# PenguinPi.net
KiCad netlist of a schematic drawn in Altium Designer
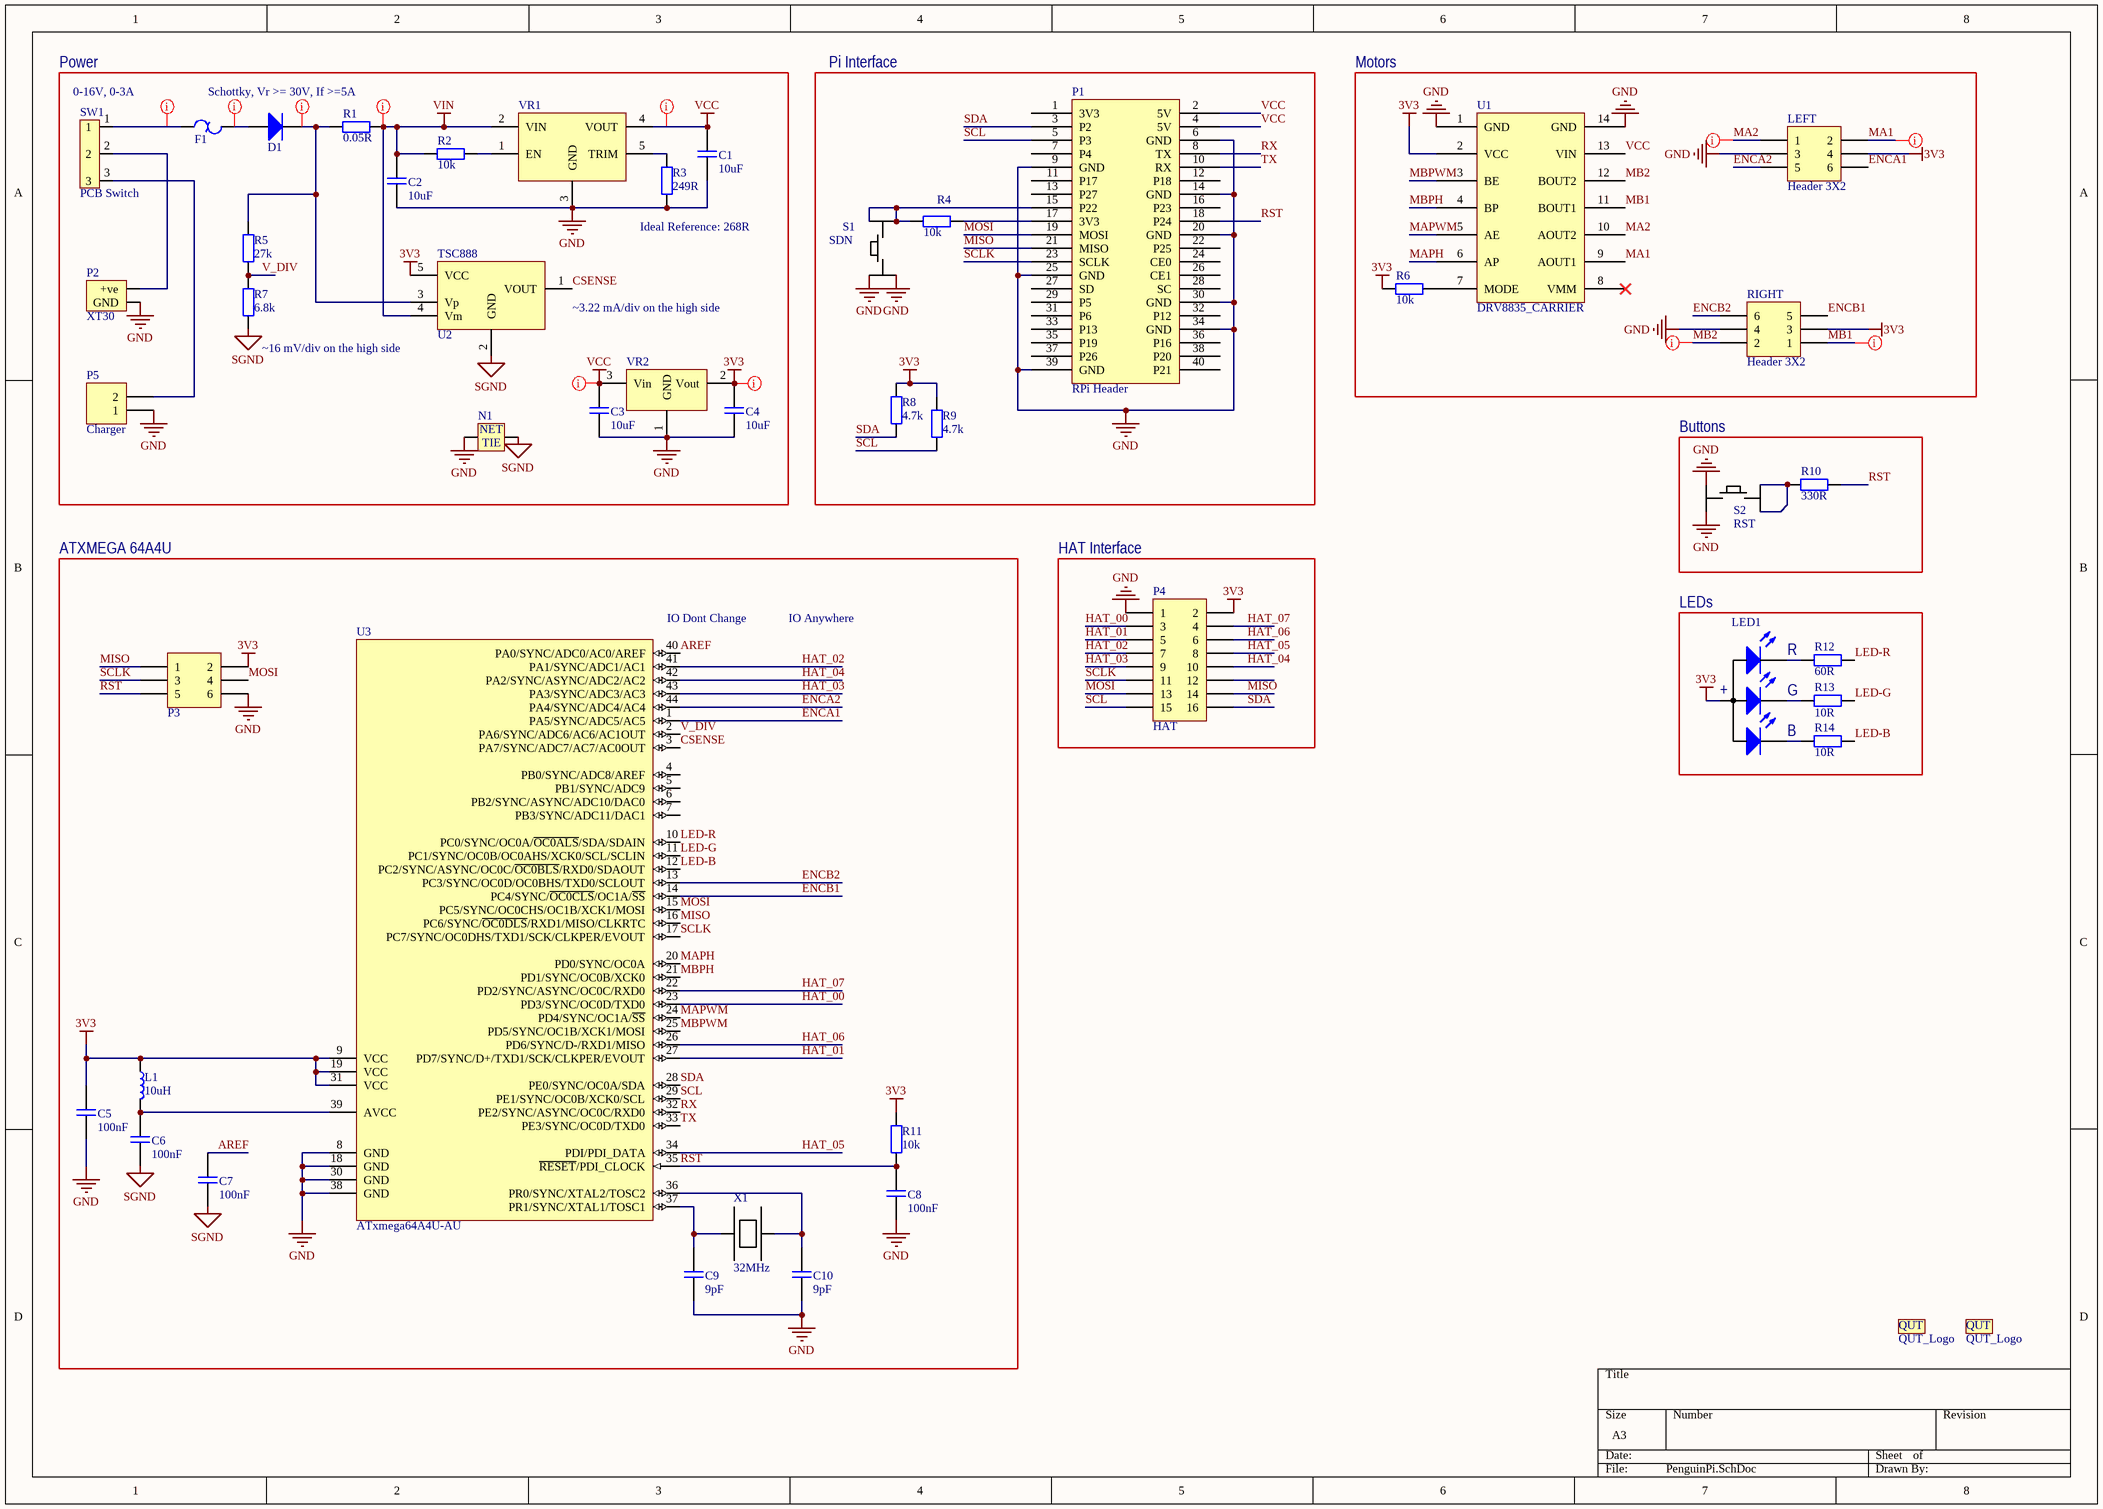
[diagram p0: PenguinPi.SchDoc]

(export (version "E")
  (design (tool "Eeschema 10.0.6"))
  (components
    (comp (ref "C1")
      (value "10uF")
      (footprint "CAPC2012X07N")
      (description "Surface mount capacitor")
      (fields (field (name "Comment") "CAP SMD"))
      (libsource (lib "Penguin") (part "CAP SMD"))
    )
    (comp (ref "C2")
      (value "10uF")
      (footprint "CAPC2012X07N")
      (description "Surface mount capacitor")
      (fields (field (name "Comment") "CAP SMD"))
      (libsource (lib "Penguin") (part "CAP SMD"))
    )
    (comp (ref "C3")
      (value "10uF")
      (footprint "CAPC2012X07N")
      (description "Surface mount capacitor")
      (fields (field (name "Comment") "CAP SMD"))
      (libsource (lib "Penguin") (part "CAP SMD"))
    )
    (comp (ref "C4")
      (value "10uF")
      (footprint "CAPC2012X07N")
      (description "Surface mount capacitor")
      (fields (field (name "Comment") "CAP SMD"))
      (libsource (lib "Penguin") (part "CAP SMD"))
    )
    (comp (ref "C5")
      (value "100nF")
      (footprint "CAPC2012X07N")
      (description "Surface mount capacitor")
      (fields (field (name "Comment") "CAP SMD"))
      (libsource (lib "Penguin") (part "CAP SMD"))
    )
    (comp (ref "C6")
      (value "100nF")
      (footprint "CAPC2012X07N")
      (description "Surface mount capacitor")
      (fields (field (name "Comment") "CAP SMD"))
      (libsource (lib "Penguin") (part "CAP SMD"))
    )
    (comp (ref "C7")
      (value "100nF")
      (footprint "CAPC2012X07N")
      (description "Surface mount capacitor")
      (fields (field (name "Comment") "CAP SMD"))
      (libsource (lib "Penguin") (part "CAP SMD"))
    )
    (comp (ref "C8")
      (value "100nF")
      (footprint "CAPC2012X07N")
      (description "Surface mount capacitor")
      (fields (field (name "Comment") "CAP SMD"))
      (libsource (lib "Penguin") (part "CAP SMD"))
    )
    (comp (ref "C9")
      (value "9pF")
      (footprint "CAPC2012X07N")
      (description "Surface mount capacitor")
      (fields (field (name "Comment") "CAP SMD"))
      (libsource (lib "Penguin") (part "CAP SMD"))
    )
    (comp (ref "C10")
      (value "9pF")
      (footprint "CAPC2012X07N")
      (description "Surface mount capacitor")
      (fields (field (name "Comment") "CAP SMD"))
      (libsource (lib "Penguin") (part "CAP SMD"))
    )
    (comp (ref "D1")
      (value "SMD DIODE")
      (footprint "SODFL470X110-2N")
      (description "Surface mount Diode")
      (libsource (lib "Penguin") (part "SMD DIODE"))
    )
    (comp (ref "F1")
      (value "RGEF250")
      (footprint "MF-MSMF250/16X-2")
      (description "PPTC Thermal Fuse")
      (libsource (lib "Penguin") (part "RGEF250"))
    )
    (comp (ref "L1")
      (value "10uH")
      (footprint "CM322522")
      (description "Surface Mount Inductor - varying sizes")
      (fields (field (name "Comment") "INDUCTOR SMD"))
      (libsource (lib "Penguin") (part "INDUCTOR SMD"))
    )
    (comp (ref "LED1")
      (value "RGB SMD")
      (footprint "RGB SMD")
      (description "ASMB-MTB1-0A3A2")
      (libsource (lib "Penguin") (part "RGB SMD"))
    )
    (comp (ref "LEFT")
      (value "Header 3X2")
      (footprint "HDR2X3")
      (description "Header, 3-Pin, Dual row")
      (fields (field (name "PUBLISHER") "Altium Limited"))
      (libsource (lib "Miscellaneous Connectors") (part "Header 3X2"))
    )
    (comp (ref "LG1") (value "QUT_Logo") (footprint "QUT_Logo") (libsource (lib "Penguin") (part "QUT_Logo")))
    (comp (ref "LG2") (value "QUT_Logo") (footprint "QUT_Logo") (libsource (lib "Penguin") (part "QUT_Logo")))
    (comp (ref "N1")
      (value "NETTIE")
      (footprint "NETTIE-SMD-5mil")
      (libsource (lib "Penguin") (part "NETTIE"))
    )
    (comp (ref "P1")
      (value "RPi Header")
      (footprint "RPI 2 Header")
      (description "GPIO connector for Raspberry Pi Microcomputer")
      (libsource (lib "Penguin") (part "RPi 2 Header"))
    )
    (comp (ref "P2") (value "XT30") (footprint "XT30 - PCB mount") (libsource (lib "QUT") (part "XT30")))
    (comp (ref "P3")
      (value "Header 3x2")
      (footprint "Header 3x2 nonstandard")
      (description "3 by 2 header, staggered pin arrangement")
      (libsource (lib "Penguin") (part "Header 3x2 Staggered"))
    )
    (comp (ref "P4")
      (value "HAT")
      (footprint "HDR2X8")
      (description "Header, 8-Pin, Dual row")
      (fields (field (name "PUBLISHER") "Altium Limited"))
      (libsource (lib "Miscellaneous Connectors") (part "Header 8X2"))
    )
    (comp (ref "P5")
      (value "Charger")
      (footprint "HDR1X2")
      (description "Header, 2-Pin")
      (fields (field (name "PUBLISHER") "Altium Limited"))
      (libsource (lib "Miscellaneous Connectors") (part "Header 2"))
    )
    (comp (ref "R1")
      (value "0.05R")
      (footprint "RESC3216X06M")
      (description "0805 surface mount resistor")
      (fields (field (name "Comment") "RES SMD"))
      (libsource (lib "") (part "RES SMD_3"))
    )
    (comp (ref "R2")
      (value "10k")
      (footprint "RESC2012X07N")
      (description "0805 surface mount resistor")
      (fields (field (name "Comment") "RES SMD"))
      (libsource (lib "Penguin") (part "RES SMD"))
    )
    (comp (ref "R3")
      (value "249R")
      (footprint "RESC2012X07N")
      (description "0805 surface mount resistor")
      (fields (field (name "Comment") "RES SMD"))
      (libsource (lib "") (part "RES SMD_1"))
    )
    (comp (ref "R4")
      (value "10k")
      (footprint "RESC2012X07N")
      (description "0805 surface mount resistor")
      (fields (field (name "Comment") "RES SMD"))
      (libsource (lib "") (part "RES SMD_2"))
    )
    (comp (ref "R5")
      (value "27k")
      (footprint "RESC2012X07N")
      (description "0805 surface mount resistor")
      (fields (field (name "Comment") "RES SMD"))
      (libsource (lib "") (part "RES SMD_1"))
    )
    (comp (ref "R6")
      (value "10k")
      (footprint "RESC2012X07N")
      (description "0805 surface mount resistor")
      (fields (field (name "Comment") "RES SMD"))
      (libsource (lib "") (part "RES SMD_2"))
    )
    (comp (ref "R7")
      (value "6.8k")
      (footprint "RESC2012X07N")
      (description "0805 surface mount resistor")
      (fields (field (name "Comment") "RES SMD"))
      (libsource (lib "") (part "RES SMD_1"))
    )
    (comp (ref "R8")
      (value "4.7k")
      (footprint "RESC2012X07N")
      (description "0805 surface mount resistor")
      (fields (field (name "Comment") "RES SMD"))
      (libsource (lib "") (part "RES SMD_1"))
    )
    (comp (ref "R9")
      (value "4.7k")
      (footprint "RESC2012X07N")
      (description "0805 surface mount resistor")
      (fields (field (name "Comment") "RES SMD"))
      (libsource (lib "") (part "RES SMD_1"))
    )
    (comp (ref "R10")
      (value "330R")
      (footprint "RESC2012X07N")
      (description "0805 surface mount resistor")
      (fields (field (name "Comment") "RES SMD"))
      (libsource (lib "") (part "RES SMD_2"))
    )
    (comp (ref "R11")
      (value "10k")
      (footprint "RESC2012X07N")
      (description "0805 surface mount resistor")
      (fields (field (name "Comment") "RES SMD"))
      (libsource (lib "") (part "RES SMD_1"))
    )
    (comp (ref "R12")
      (value "60R")
      (footprint "RESC2012X07N")
      (description "0805 surface mount resistor")
      (fields (field (name "Comment") "RES SMD"))
      (libsource (lib "") (part "RES SMD_2"))
    )
    (comp (ref "R13")
      (value "10R")
      (footprint "RESC2012X07N")
      (description "0805 surface mount resistor")
      (fields (field (name "Comment") "RES SMD"))
      (libsource (lib "") (part "RES SMD_2"))
    )
    (comp (ref "R14")
      (value "10R")
      (footprint "RESC2012X07N")
      (description "0805 surface mount resistor")
      (fields (field (name "Comment") "RES SMD"))
      (libsource (lib "") (part "RES SMD_2"))
    )
    (comp (ref "RIGHT")
      (value "Header 3X2")
      (footprint "HDR2X3")
      (description "Header, 3-Pin, Dual row")
      (fields (field (name "PUBLISHER") "Altium Limited"))
      (libsource (lib "") (part "Header 3X2_1"))
    )
    (comp (ref "S1")
      (value "SDN")
      (footprint "E-SWITCH-TL3342")
      (description "TL 3342 surface mount pushbutton")
      (libsource (lib "Penguin") (part "E-SWITCH-PUSHBUTTON"))
    )
    (comp (ref "S2")
      (value "RST")
      (footprint "E-SWITCH-TL3342")
      (description "TL 3342 surface mount pushbutton")
      (libsource (lib "Penguin") (part "E-SWITCH-PUSHBUTTON"))
    )
    (comp (ref "SW1")
      (value "PCB Switch")
      (footprint "PCB Switch")
      (libsource (lib "PenguinPi_v2") (part "PCB Switch"))
    )
    (comp (ref "U1")
      (value "DRV8835_CARRIER")
      (footprint "DRV8835_CARRIER")
      (description "DRV8835 Motor Controller")
      (libsource (lib "Penguin") (part "DRV8835_CARRIER"))
    )
    (comp (ref "U2")
      (value "TSC888")
      (footprint "SOT95P280X145-5N")
      (description "Curent Sense Amplifier")
      (libsource (lib "Penguin") (part "TSC888"))
    )
    (comp (ref "U3")
      (value "ATxmega64A4U-AU")
      (footprint "44A_L")
      (fields (field (name "MANUFACTURER") "Atmel"))
      (libsource (lib "Altium Content Vault") (part "CMP-0094-00068-2"))
    )
    (comp (ref "VR1")
      (value "MURATA_OKR-T3-W12C")
      (footprint "MURATA_OKR-Tn")
      (description "5V 3A switching voltage regulator")
      (libsource (lib "Penguin") (part "MURATA_OKR-T3-W12C"))
    )
    (comp (ref "VR2")
      (value "3V3 LDO")
      (footprint "SOT230P700X180-4N")
      (description "3.3 V Low Dropout Regulator")
      (libsource (lib "Penguin") (part "3V3 LDO"))
    )
    (comp (ref "X1")
      (value "32MHz")
      (footprint "XTAL AV Series")
      (fields (field (name "MAN PART NO") "X1E0000210162"))
      (libsource (lib "QUT") (part "XTAL"))
    )
  )
  (nets
    (net (code "1") (name "/AREF") (class "Default")
      (node (ref "C7") (pin "2") (pinfunction "K_2") (pintype "passive"))
      (node (ref "U3") (pin "40") (pinfunction "PA0/SYNC/ADC0/AC0/AREF_40") (pintype "bidirectional"))
    )
    (net (code "2") (name "/CSENSE") (class "Default")
      (node (ref "U2") (pin "1") (pinfunction "VOUT_1") (pintype "passive"))
      (node (ref "U3") (pin "3") (pinfunction "PA7/SYNC/ADC7/AC7/AC0OUT_3") (pintype "bidirectional"))
    )
    (net (code "3") (name "/ENCA1") (class "Default")
      (node (ref "LEFT") (pin "6") (pinfunction "6_6") (pintype "passive"))
      (node (ref "U3") (pin "1") (pinfunction "PA5/SYNC/ADC5/AC5_1") (pintype "bidirectional"))
    )
    (net (code "4") (name "/ENCA2") (class "Default")
      (node (ref "LEFT") (pin "5") (pinfunction "5_5") (pintype "passive"))
      (node (ref "U3") (pin "44") (pinfunction "PA4/SYNC/ADC4/AC4_44") (pintype "bidirectional"))
    )
    (net (code "5") (name "/ENCB1") (class "Default")
      (node (ref "RIGHT") (pin "5") (pinfunction "5_5") (pintype "passive"))
      (node (ref "U3") (pin "14") (pinfunction "PC4/SYNC/~{OC0CLS}/OC1A/~{SS}_14") (pintype "bidirectional"))
    )
    (net (code "6") (name "/ENCB2") (class "Default")
      (node (ref "RIGHT") (pin "6") (pinfunction "6_6") (pintype "passive"))
      (node (ref "U3") (pin "13") (pinfunction "PC3/SYNC/OC0D/OC0BHS/TXD0/SCLOUT_13") (pintype "bidirectional"))
    )
    (net (code "7") (name "/HAT_00") (class "Default")
      (node (ref "P4") (pin "3") (pinfunction "3_3") (pintype "passive"))
      (node (ref "U3") (pin "23") (pinfunction "PD3/SYNC/OC0D/TXD0_23") (pintype "bidirectional"))
    )
    (net (code "8") (name "/HAT_01") (class "Default")
      (node (ref "P4") (pin "5") (pinfunction "5_5") (pintype "passive"))
      (node (ref "U3") (pin "27") (pinfunction "PD7/SYNC/D+/TXD1/SCK/CLKPER/EVOUT_27") (pintype "bidirectional"))
    )
    (net (code "9") (name "/HAT_02") (class "Default")
      (node (ref "P4") (pin "7") (pinfunction "7_7") (pintype "passive"))
      (node (ref "U3") (pin "41") (pinfunction "PA1/SYNC/ADC1/AC1_41") (pintype "bidirectional"))
    )
    (net (code "10") (name "/HAT_03") (class "Default")
      (node (ref "P4") (pin "9") (pinfunction "9_9") (pintype "passive"))
      (node (ref "U3") (pin "43") (pinfunction "PA3/SYNC/ADC3/AC3_43") (pintype "bidirectional"))
    )
    (net (code "11") (name "/HAT_04") (class "Default")
      (node (ref "P4") (pin "10") (pinfunction "10_10") (pintype "passive"))
      (node (ref "U3") (pin "42") (pinfunction "PA2/SYNC/ASYNC/ADC2/AC2_42") (pintype "bidirectional"))
    )
    (net (code "12") (name "/HAT_05") (class "Default")
      (node (ref "P4") (pin "8") (pinfunction "8_8") (pintype "passive"))
      (node (ref "U3") (pin "34") (pinfunction "PDI/PDI_DATA_34") (pintype "bidirectional"))
    )
    (net (code "13") (name "/HAT_06") (class "Default")
      (node (ref "P4") (pin "6") (pinfunction "6_6") (pintype "passive"))
      (node (ref "U3") (pin "26") (pinfunction "PD6/SYNC/D-/RXD1/MISO_26") (pintype "bidirectional"))
    )
    (net (code "14") (name "/HAT_07") (class "Default")
      (node (ref "P4") (pin "4") (pinfunction "4_4") (pintype "passive"))
      (node (ref "U3") (pin "22") (pinfunction "PD2/SYNC/ASYNC/OC0C/RXD0_22") (pintype "bidirectional"))
    )
    (net (code "15") (name "/LED-B") (class "Default")
      (node (ref "R14") (pin "2") (pinfunction "2_2") (pintype "passive"))
      (node (ref "U3") (pin "12") (pinfunction "PC2/SYNC/ASYNC/OC0C/~{OC0BLS}/RXD0/SDAOUT_12") (pintype "bidirectional"))
    )
    (net (code "16") (name "/LED-G") (class "Default")
      (node (ref "R13") (pin "2") (pinfunction "2_2") (pintype "passive"))
      (node (ref "U3") (pin "11") (pinfunction "PC1/SYNC/OC0B/OC0AHS/XCK0/SCL/SCLIN_11") (pintype "bidirectional"))
    )
    (net (code "17") (name "/LED-R") (class "Default")
      (node (ref "R12") (pin "2") (pinfunction "2_2") (pintype "passive"))
      (node (ref "U3") (pin "10") (pinfunction "PC0/SYNC/OC0A/~{OC0ALS}/SDA/SDAIN_10") (pintype "bidirectional"))
    )
    (net (code "18") (name "/MA1") (class "Default")
      (node (ref "LEFT") (pin "2") (pinfunction "2_2") (pintype "passive"))
      (node (ref "U1") (pin "9") (pinfunction "AOUT1_9") (pintype "passive"))
    )
    (net (code "19") (name "/MA2") (class "Default")
      (node (ref "LEFT") (pin "1") (pinfunction "1_1") (pintype "passive"))
      (node (ref "U1") (pin "10") (pinfunction "AOUT2_10") (pintype "passive"))
    )
    (net (code "20") (name "/MAPH") (class "Default")
      (node (ref "U1") (pin "6") (pinfunction "AP_6") (pintype "passive"))
      (node (ref "U3") (pin "20") (pinfunction "PD0/SYNC/OC0A_20") (pintype "bidirectional"))
    )
    (net (code "21") (name "/MAPWM") (class "Default")
      (node (ref "U1") (pin "5") (pinfunction "AE_5") (pintype "passive"))
      (node (ref "U3") (pin "24") (pinfunction "PD4/SYNC/OC1A/~{SS}_24") (pintype "bidirectional"))
    )
    (net (code "22") (name "/MB1") (class "Default")
      (node (ref "RIGHT") (pin "1") (pinfunction "1_1") (pintype "passive"))
      (node (ref "U1") (pin "11") (pinfunction "BOUT1_11") (pintype "passive"))
    )
    (net (code "23") (name "/MB2") (class "Default")
      (node (ref "RIGHT") (pin "2") (pinfunction "2_2") (pintype "passive"))
      (node (ref "U1") (pin "12") (pinfunction "BOUT2_12") (pintype "passive"))
    )
    (net (code "24") (name "/MBPH") (class "Default")
      (node (ref "U1") (pin "4") (pinfunction "BP_4") (pintype "passive"))
      (node (ref "U3") (pin "21") (pinfunction "PD1/SYNC/OC0B/XCK0_21") (pintype "bidirectional"))
    )
    (net (code "25") (name "/MBPWM") (class "Default")
      (node (ref "U1") (pin "3") (pinfunction "BE_3") (pintype "passive"))
      (node (ref "U3") (pin "25") (pinfunction "PD5/SYNC/OC1B/XCK1/MOSI_25") (pintype "bidirectional"))
    )
    (net (code "26") (name "/MISO") (class "Default")
      (node (ref "P1") (pin "21") (pinfunction "MISO_21") (pintype "passive"))
      (node (ref "P3") (pin "1") (pinfunction "1_1") (pintype "passive"))
      (node (ref "P4") (pin "14") (pinfunction "14_14") (pintype "passive"))
      (node (ref "U3") (pin "16") (pinfunction "PC6/SYNC/~{OC0DLS}/RXD1/MISO/CLKRTC_16") (pintype "bidirectional"))
    )
    (net (code "27") (name "/MOSI") (class "Default")
      (node (ref "P1") (pin "19") (pinfunction "MOSI_19") (pintype "passive"))
      (node (ref "P3") (pin "4") (pinfunction "4_4") (pintype "passive"))
      (node (ref "P4") (pin "13") (pinfunction "13_13") (pintype "passive"))
      (node (ref "U3") (pin "15") (pinfunction "PC5/SYNC/OC0CHS/OC1B/XCK1/MOSI_15") (pintype "bidirectional"))
    )
    (net (code "28") (name "/RST") (class "Default")
      (node (ref "C8") (pin "2") (pinfunction "K_2") (pintype "passive"))
      (node (ref "P1") (pin "18") (pinfunction "P24_18") (pintype "passive"))
      (node (ref "P3") (pin "5") (pinfunction "5_5") (pintype "passive"))
      (node (ref "R10") (pin "2") (pinfunction "2_2") (pintype "passive"))
      (node (ref "R11") (pin "1") (pinfunction "1_1") (pintype "passive"))
      (node (ref "U3") (pin "35") (pinfunction "~{RESET}/PDI_CLOCK_35") (pintype "input"))
    )
    (net (code "29") (name "/RX") (class "Default")
      (node (ref "P1") (pin "8") (pinfunction "TX_8") (pintype "passive"))
      (node (ref "U3") (pin "32") (pinfunction "PE2/SYNC/ASYNC/OC0C/RXD0_32") (pintype "bidirectional"))
    )
    (net (code "30") (name "/SCL") (class "Default")
      (node (ref "P1") (pin "5") (pinfunction "P3_5") (pintype "passive"))
      (node (ref "P4") (pin "15") (pinfunction "15_15") (pintype "passive"))
      (node (ref "R9") (pin "1") (pinfunction "1_1") (pintype "passive"))
      (node (ref "U3") (pin "29") (pinfunction "PE1/SYNC/OC0B/XCK0/SCL_29") (pintype "bidirectional"))
    )
    (net (code "31") (name "/SCLK") (class "Default")
      (node (ref "P1") (pin "23") (pinfunction "SCLK_23") (pintype "passive"))
      (node (ref "P3") (pin "3") (pinfunction "3_3") (pintype "passive"))
      (node (ref "P4") (pin "11") (pinfunction "11_11") (pintype "passive"))
      (node (ref "U3") (pin "17") (pinfunction "PC7/SYNC/OC0DHS/TXD1/SCK/CLKPER/EVOUT_17") (pintype "bidirectional"))
    )
    (net (code "32") (name "/SDA") (class "Default")
      (node (ref "P1") (pin "3") (pinfunction "P2_3") (pintype "passive"))
      (node (ref "P4") (pin "16") (pinfunction "16_16") (pintype "passive"))
      (node (ref "R8") (pin "1") (pinfunction "1_1") (pintype "passive"))
      (node (ref "U3") (pin "28") (pinfunction "PE0/SYNC/OC0A/SDA_28") (pintype "bidirectional"))
    )
    (net (code "33") (name "/TX") (class "Default")
      (node (ref "P1") (pin "10") (pinfunction "RX_10") (pintype "passive"))
      (node (ref "U3") (pin "33") (pinfunction "PE3/SYNC/OC0D/TXD0_33") (pintype "bidirectional"))
    )
    (net (code "34") (name "/V_DIV") (class "Default")
      (node (ref "R5") (pin "1") (pinfunction "1_1") (pintype "passive"))
      (node (ref "R7") (pin "2") (pinfunction "2_2") (pintype "passive"))
      (node (ref "U3") (pin "2") (pinfunction "PA6/SYNC/ADC6/AC6/AC1OUT_2") (pintype "bidirectional"))
    )
    (net (code "35") (name "3V3") (class "Default")
      (node (ref "C4") (pin "2") (pinfunction "K_2") (pintype "passive"))
      (node (ref "C5") (pin "2") (pinfunction "K_2") (pintype "passive"))
      (node (ref "L1") (pin "1") (pinfunction "Anode_1") (pintype "passive"))
      (node (ref "LED1") (pin "4") (pinfunction "A_4") (pintype "passive"))
      (node (ref "LEFT") (pin "4") (pinfunction "4_4") (pintype "passive"))
      (node (ref "P3") (pin "2") (pinfunction "2_2") (pintype "passive"))
      (node (ref "P4") (pin "2") (pinfunction "2_2") (pintype "passive"))
      (node (ref "R11") (pin "2") (pinfunction "2_2") (pintype "passive"))
      (node (ref "R6") (pin "1") (pinfunction "1_1") (pintype "passive"))
      (node (ref "R8") (pin "2") (pinfunction "2_2") (pintype "passive"))
      (node (ref "R9") (pin "2") (pinfunction "2_2") (pintype "passive"))
      (node (ref "RIGHT") (pin "3") (pinfunction "3_3") (pintype "passive"))
      (node (ref "U1") (pin "2") (pinfunction "VCC_2") (pintype "passive"))
      (node (ref "U2") (pin "5") (pinfunction "VCC_5") (pintype "passive"))
      (node (ref "U3") (pin "19") (pinfunction "VCC_19") (pintype "power_in"))
      (node (ref "U3") (pin "31") (pinfunction "VCC_31") (pintype "power_in"))
      (node (ref "U3") (pin "9") (pinfunction "VCC_9") (pintype "power_in"))
      (node (ref "VR2") (pin "2") (pinfunction "Vout_2") (pintype "passive"))
    )
    (net (code "36") (name "GND") (class "Default")
      (node (ref "C1") (pin "1") (pinfunction "A_1") (pintype "passive"))
      (node (ref "C10") (pin "1") (pinfunction "A_1") (pintype "passive"))
      (node (ref "C2") (pin "1") (pinfunction "A_1") (pintype "passive"))
      (node (ref "C3") (pin "1") (pinfunction "A_1") (pintype "passive"))
      (node (ref "C4") (pin "1") (pinfunction "A_1") (pintype "passive"))
      (node (ref "C5") (pin "1") (pinfunction "A_1") (pintype "passive"))
      (node (ref "C8") (pin "1") (pinfunction "A_1") (pintype "passive"))
      (node (ref "C9") (pin "1") (pinfunction "A_1") (pintype "passive"))
      (node (ref "LEFT") (pin "3") (pinfunction "3_3") (pintype "passive"))
      (node (ref "N1") (pin "1") (pinfunction "1_1") (pintype "passive"))
      (node (ref "P1") (pin "14") (pinfunction "GND_14") (pintype "passive"))
      (node (ref "P1") (pin "20") (pinfunction "GND_20") (pintype "passive"))
      (node (ref "P1") (pin "25") (pinfunction "GND_25") (pintype "passive"))
      (node (ref "P1") (pin "30") (pinfunction "GND_30") (pintype "passive"))
      (node (ref "P1") (pin "34") (pinfunction "GND_34") (pintype "passive"))
      (node (ref "P1") (pin "39") (pinfunction "GND_39") (pintype "passive"))
      (node (ref "P1") (pin "6") (pinfunction "GND_6") (pintype "passive"))
      (node (ref "P1") (pin "9") (pinfunction "GND_9") (pintype "passive"))
      (node (ref "P2") (pin "1") (pinfunction "GND_1") (pintype "passive"))
      (node (ref "P3") (pin "6") (pinfunction "6_6") (pintype "passive"))
      (node (ref "P4") (pin "1") (pinfunction "1_1") (pintype "passive"))
      (node (ref "P5") (pin "1") (pinfunction "1_1") (pintype "passive"))
      (node (ref "R3") (pin "1") (pinfunction "1_1") (pintype "passive"))
      (node (ref "RIGHT") (pin "4") (pinfunction "4_4") (pintype "passive"))
      (node (ref "S1") (pin "3") (pinfunction "B'_3") (pintype "passive"))
      (node (ref "S1") (pin "4") (pinfunction "B_4") (pintype "passive"))
      (node (ref "S2") (pin "1") (pinfunction "A_1") (pintype "passive"))
      (node (ref "S2") (pin "2") (pinfunction "A'_2") (pintype "passive"))
      (node (ref "U1") (pin "1") (pinfunction "GND_1") (pintype "passive"))
      (node (ref "U1") (pin "14") (pinfunction "GND_14") (pintype "passive"))
      (node (ref "U3") (pin "18") (pinfunction "GND_18") (pintype "power_in"))
      (node (ref "U3") (pin "30") (pinfunction "GND_30") (pintype "power_in"))
      (node (ref "U3") (pin "38") (pinfunction "GND_38") (pintype "power_in"))
      (node (ref "U3") (pin "8") (pinfunction "GND_8") (pintype "power_in"))
      (node (ref "VR1") (pin "3") (pinfunction "GND_3") (pintype "power_in"))
      (node (ref "VR2") (pin "1") (pinfunction "GND_1") (pintype "passive"))
    )
    (net (code "37") (name "Net-(C6-K)") (class "Default")
      (node (ref "C6") (pin "2") (pinfunction "K_2") (pintype "passive"))
      (node (ref "L1") (pin "2") (pinfunction "Cathode_2") (pintype "passive"))
      (node (ref "U3") (pin "39") (pinfunction "AVCC_39") (pintype "power_in"))
    )
    (net (code "38") (name "Net-(C9-K)") (class "Default")
      (node (ref "C9") (pin "2") (pinfunction "K_2") (pintype "passive"))
      (node (ref "U3") (pin "37") (pinfunction "PR1/SYNC/XTAL1/TOSC1_37") (pintype "bidirectional"))
      (node (ref "X1") (pin "2") (pinfunction "2_2") (pintype "passive"))
    )
    (net (code "39") (name "Net-(C10-K)") (class "Default")
      (node (ref "C10") (pin "2") (pinfunction "K_2") (pintype "passive"))
      (node (ref "U3") (pin "36") (pinfunction "PR0/SYNC/XTAL2/TOSC2_36") (pintype "bidirectional"))
      (node (ref "X1") (pin "1") (pinfunction "1_1") (pintype "passive"))
    )
    (net (code "40") (name "Net-(D1-Pad1)") (class "Default")
      (node (ref "D1") (pin "1") (pinfunction "1_1") (pintype "power_in"))
      (node (ref "F1") (pin "2") (pinfunction "2_2") (pintype "power_in"))
    )
    (net (code "41") (name "Net-(F1-Pad1)") (class "Default")
      (node (ref "F1") (pin "1") (pinfunction "1_1") (pintype "power_in"))
      (node (ref "SW1") (pin "1") (pinfunction "1_1") (pintype "passive"))
    )
    (net (code "42") (name "Net-(LED1-K-B)") (class "Default")
      (node (ref "LED1") (pin "3") (pinfunction "K-B_3") (pintype "passive"))
      (node (ref "R14") (pin "1") (pinfunction "1_1") (pintype "passive"))
    )
    (net (code "43") (name "Net-(LED1-K-G)") (class "Default")
      (node (ref "LED1") (pin "2") (pinfunction "K-G_2") (pintype "passive"))
      (node (ref "R13") (pin "1") (pinfunction "1_1") (pintype "passive"))
    )
    (net (code "44") (name "Net-(LED1-K-R)") (class "Default")
      (node (ref "LED1") (pin "1") (pinfunction "K-R_1") (pintype "passive"))
      (node (ref "R12") (pin "1") (pinfunction "1_1") (pintype "passive"))
    )
    (net (code "45") (name "Net-(P1-3V3-Pad17)") (class "Default")
      (node (ref "P1") (pin "17") (pinfunction "3V3_17") (pintype "passive"))
      (node (ref "R4") (pin "2") (pinfunction "2_2") (pintype "passive"))
    )
    (net (code "46") (name "Net-(P1-P22)") (class "Default")
      (node (ref "P1") (pin "15") (pinfunction "P22_15") (pintype "passive"))
      (node (ref "R4") (pin "1") (pinfunction "1_1") (pintype "passive"))
      (node (ref "S1") (pin "1") (pinfunction "A_1") (pintype "passive"))
      (node (ref "S1") (pin "2") (pinfunction "A'_2") (pintype "passive"))
    )
    (net (code "47") (name "Net-(P2-+ve)") (class "Default")
      (node (ref "P2") (pin "2") (pinfunction "+ve_2") (pintype "passive"))
      (node (ref "SW1") (pin "2") (pinfunction "2_2") (pintype "passive"))
    )
    (net (code "48") (name "Net-(P5-Pad2)") (class "Default")
      (node (ref "P5") (pin "2") (pinfunction "2_2") (pintype "passive"))
      (node (ref "SW1") (pin "3") (pinfunction "3_3") (pintype "passive"))
    )
    (net (code "49") (name "Net-(S2-B')") (class "Default")
      (node (ref "R10") (pin "1") (pinfunction "1_1") (pintype "passive"))
      (node (ref "S2") (pin "3") (pinfunction "B'_3") (pintype "passive"))
      (node (ref "S2") (pin "4") (pinfunction "B_4") (pintype "passive"))
    )
    (net (code "50") (name "Net-(U1-MODE)") (class "Default")
      (node (ref "R6") (pin "2") (pinfunction "2_2") (pintype "passive"))
      (node (ref "U1") (pin "7") (pinfunction "MODE_7") (pintype "passive"))
    )
    (net (code "51") (name "Net-(U2-Vp)") (class "Default")
      (node (ref "D1") (pin "2") (pinfunction "2_2") (pintype "power_in"))
      (node (ref "R1") (pin "1") (pinfunction "1_1") (pintype "power_in"))
      (node (ref "R5") (pin "2") (pinfunction "2_2") (pintype "passive"))
      (node (ref "U2") (pin "3") (pinfunction "Vp_3") (pintype "passive"))
    )
    (net (code "52") (name "Net-(VR1-EN)") (class "Default")
      (node (ref "R2") (pin "1") (pinfunction "1_1") (pintype "passive"))
      (node (ref "VR1") (pin "1") (pinfunction "EN_1") (pintype "passive"))
    )
    (net (code "53") (name "Net-(VR1-TRIM)") (class "Default")
      (node (ref "R3") (pin "2") (pinfunction "2_2") (pintype "passive"))
      (node (ref "VR1") (pin "5") (pinfunction "TRIM_5") (pintype "passive"))
    )
    (net (code "54") (name "SGND") (class "Default")
      (node (ref "C6") (pin "1") (pinfunction "A_1") (pintype "passive"))
      (node (ref "C7") (pin "1") (pinfunction "A_1") (pintype "passive"))
      (node (ref "N1") (pin "2") (pinfunction "2_2") (pintype "passive"))
      (node (ref "R7") (pin "1") (pinfunction "1_1") (pintype "passive"))
      (node (ref "U2") (pin "2") (pinfunction "GND_2") (pintype "passive"))
    )
    (net (code "55") (name "VCC") (class "Default")
      (node (ref "C1") (pin "2") (pinfunction "K_2") (pintype "passive"))
      (node (ref "C3") (pin "2") (pinfunction "K_2") (pintype "passive"))
      (node (ref "P1") (pin "2") (pinfunction "5V_2") (pintype "passive"))
      (node (ref "P1") (pin "4") (pinfunction "5V_4") (pintype "passive"))
      (node (ref "U1") (pin "13") (pinfunction "VIN_13") (pintype "passive"))
      (node (ref "VR1") (pin "4") (pinfunction "VOUT_4") (pintype "power_in"))
      (node (ref "VR2") (pin "3") (pinfunction "Vin_3") (pintype "passive"))
    )
    (net (code "56") (name "VIN") (class "Default")
      (node (ref "C2") (pin "2") (pinfunction "K_2") (pintype "passive"))
      (node (ref "R1") (pin "2") (pinfunction "2_2") (pintype "power_in"))
      (node (ref "R2") (pin "2") (pinfunction "2_2") (pintype "passive"))
      (node (ref "U2") (pin "4") (pinfunction "Vm_4") (pintype "passive"))
      (node (ref "VR1") (pin "2") (pinfunction "VIN_2") (pintype "power_in"))
    )
    (net (code "57") (name "unconnected-(P1-3V3-Pad1)") (class "Default")
      (node (ref "P1") (pin "1") (pinfunction "3V3_1") (pintype "passive"))
    )
    (net (code "58") (name "unconnected-(P1-CE0-Pad24)") (class "Default")
      (node (ref "P1") (pin "24") (pinfunction "CE0_24") (pintype "passive"))
    )
    (net (code "59") (name "unconnected-(P1-CE1-Pad26)") (class "Default")
      (node (ref "P1") (pin "26") (pinfunction "CE1_26") (pintype "passive"))
    )
    (net (code "60") (name "unconnected-(P1-P4-Pad7)") (class "Default")
      (node (ref "P1") (pin "7") (pinfunction "P4_7") (pintype "passive"))
    )
    (net (code "61") (name "unconnected-(P1-P5-Pad29)") (class "Default")
      (node (ref "P1") (pin "29") (pinfunction "P5_29") (pintype "passive"))
    )
    (net (code "62") (name "unconnected-(P1-P6-Pad31)") (class "Default")
      (node (ref "P1") (pin "31") (pinfunction "P6_31") (pintype "passive"))
    )
    (net (code "63") (name "unconnected-(P1-P12-Pad32)") (class "Default")
      (node (ref "P1") (pin "32") (pinfunction "P12_32") (pintype "passive"))
    )
    (net (code "64") (name "unconnected-(P1-P13-Pad33)") (class "Default")
      (node (ref "P1") (pin "33") (pinfunction "P13_33") (pintype "passive"))
    )
    (net (code "65") (name "unconnected-(P1-P16-Pad36)") (class "Default")
      (node (ref "P1") (pin "36") (pinfunction "P16_36") (pintype "passive"))
    )
    (net (code "66") (name "unconnected-(P1-P17-Pad11)") (class "Default")
      (node (ref "P1") (pin "11") (pinfunction "P17_11") (pintype "passive"))
    )
    (net (code "67") (name "unconnected-(P1-P18-Pad12)") (class "Default")
      (node (ref "P1") (pin "12") (pinfunction "P18_12") (pintype "passive"))
    )
    (net (code "68") (name "unconnected-(P1-P19-Pad35)") (class "Default")
      (node (ref "P1") (pin "35") (pinfunction "P19_35") (pintype "passive"))
    )
    (net (code "69") (name "unconnected-(P1-P20-Pad38)") (class "Default")
      (node (ref "P1") (pin "38") (pinfunction "P20_38") (pintype "passive"))
    )
    (net (code "70") (name "unconnected-(P1-P21-Pad40)") (class "Default")
      (node (ref "P1") (pin "40") (pinfunction "P21_40") (pintype "passive"))
    )
    (net (code "71") (name "unconnected-(P1-P23-Pad16)") (class "Default")
      (node (ref "P1") (pin "16") (pinfunction "P23_16") (pintype "passive"))
    )
    (net (code "72") (name "unconnected-(P1-P25-Pad22)") (class "Default")
      (node (ref "P1") (pin "22") (pinfunction "P25_22") (pintype "passive"))
    )
    (net (code "73") (name "unconnected-(P1-P26-Pad37)") (class "Default")
      (node (ref "P1") (pin "37") (pinfunction "P26_37") (pintype "passive"))
    )
    (net (code "74") (name "unconnected-(P1-P27-Pad13)") (class "Default")
      (node (ref "P1") (pin "13") (pinfunction "P27_13") (pintype "passive"))
    )
    (net (code "75") (name "unconnected-(P1-SC-Pad28)") (class "Default")
      (node (ref "P1") (pin "28") (pinfunction "SC_28") (pintype "passive"))
    )
    (net (code "76") (name "unconnected-(P1-SD-Pad27)") (class "Default")
      (node (ref "P1") (pin "27") (pinfunction "SD_27") (pintype "passive"))
    )
    (net (code "77") (name "unconnected-(P4-Pad12)") (class "Default")
      (node (ref "P4") (pin "12") (pinfunction "12_12") (pintype "passive"))
    )
    (net (code "78") (name "unconnected-(U1-VMM-Pad8)") (class "Default")
      (node (ref "U1") (pin "8") (pinfunction "VMM_8") (pintype "passive+no_connect"))
    )
    (net (code "79") (name "unconnected-(U3-PB0{slash}SYNC{slash}ADC8{slash}AREF-Pad4)") (class "Default")
      (node (ref "U3") (pin "4") (pinfunction "PB0/SYNC/ADC8/AREF_4") (pintype "bidirectional"))
    )
    (net (code "80") (name "unconnected-(U3-PB1{slash}SYNC{slash}ADC9-Pad5)") (class "Default")
      (node (ref "U3") (pin "5") (pinfunction "PB1/SYNC/ADC9_5") (pintype "bidirectional"))
    )
    (net (code "81") (name "unconnected-(U3-PB2{slash}SYNC{slash}ASYNC{slash}ADC10{slash}DAC0-Pad6)") (class "Default")
      (node (ref "U3") (pin "6") (pinfunction "PB2/SYNC/ASYNC/ADC10/DAC0_6") (pintype "bidirectional"))
    )
    (net (code "82") (name "unconnected-(U3-PB3{slash}SYNC{slash}ADC11{slash}DAC1-Pad7)") (class "Default")
      (node (ref "U3") (pin "7") (pinfunction "PB3/SYNC/ADC11/DAC1_7") (pintype "bidirectional"))
    )
  )
)
